# VL6180.net
KiCad netlist of a schematic drawn in Altium Designer
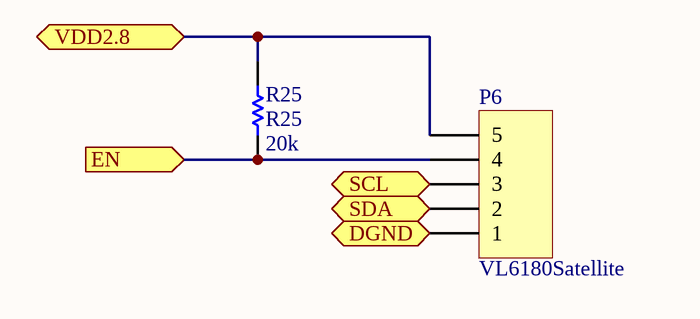
[diagram p0: VL6180.SchDoc]

(export (version "E")
  (design (tool "Eeschema 10.0.6"))
  (components
    (comp (ref "P6")
      (value "VL6180Satellite")
      (footprint "PH_5_PTH")
      (description "Header, 5-Pin")
      (fields (field (name "PUBLISHER") "Altium Limited"))
      (libsource (lib "Miscellaneous Connectors") (part "Header 5"))
    )
    (comp (ref "R25")
      (value "R25")
      (footprint "RES_0805")
      (description "Resistor")
      (fields (field (name "ALTIUM_VALUE") "20k") (field (name "PUBLISHER") "Altium Limited"))
      (libsource (lib "SmartMouse2016") (part "Res1"))
    )
  )
  (nets
    (net (code "1") (name "/DGND") (class "Default")
      (node (ref "P6") (pin "1") (pinfunction "1_1") (pintype "passive"))
    )
    (net (code "2") (name "/EN") (class "Default")
      (node (ref "P6") (pin "4") (pinfunction "4_4") (pintype "passive"))
      (node (ref "R25") (pin "1") (pinfunction "1_1") (pintype "passive"))
    )
    (net (code "3") (name "/SCL") (class "Default")
      (node (ref "P6") (pin "3") (pinfunction "3_3") (pintype "passive"))
    )
    (net (code "4") (name "/SDA") (class "Default")
      (node (ref "P6") (pin "2") (pinfunction "2_2") (pintype "passive"))
    )
    (net (code "5") (name "/VDD2.8") (class "Default")
      (node (ref "P6") (pin "5") (pinfunction "5_5") (pintype "passive"))
      (node (ref "R25") (pin "2") (pinfunction "2_2") (pintype "passive"))
    )
  )
)
